# perfect_cubev2.net
KiCad netlist of a schematic drawn in EAGLE
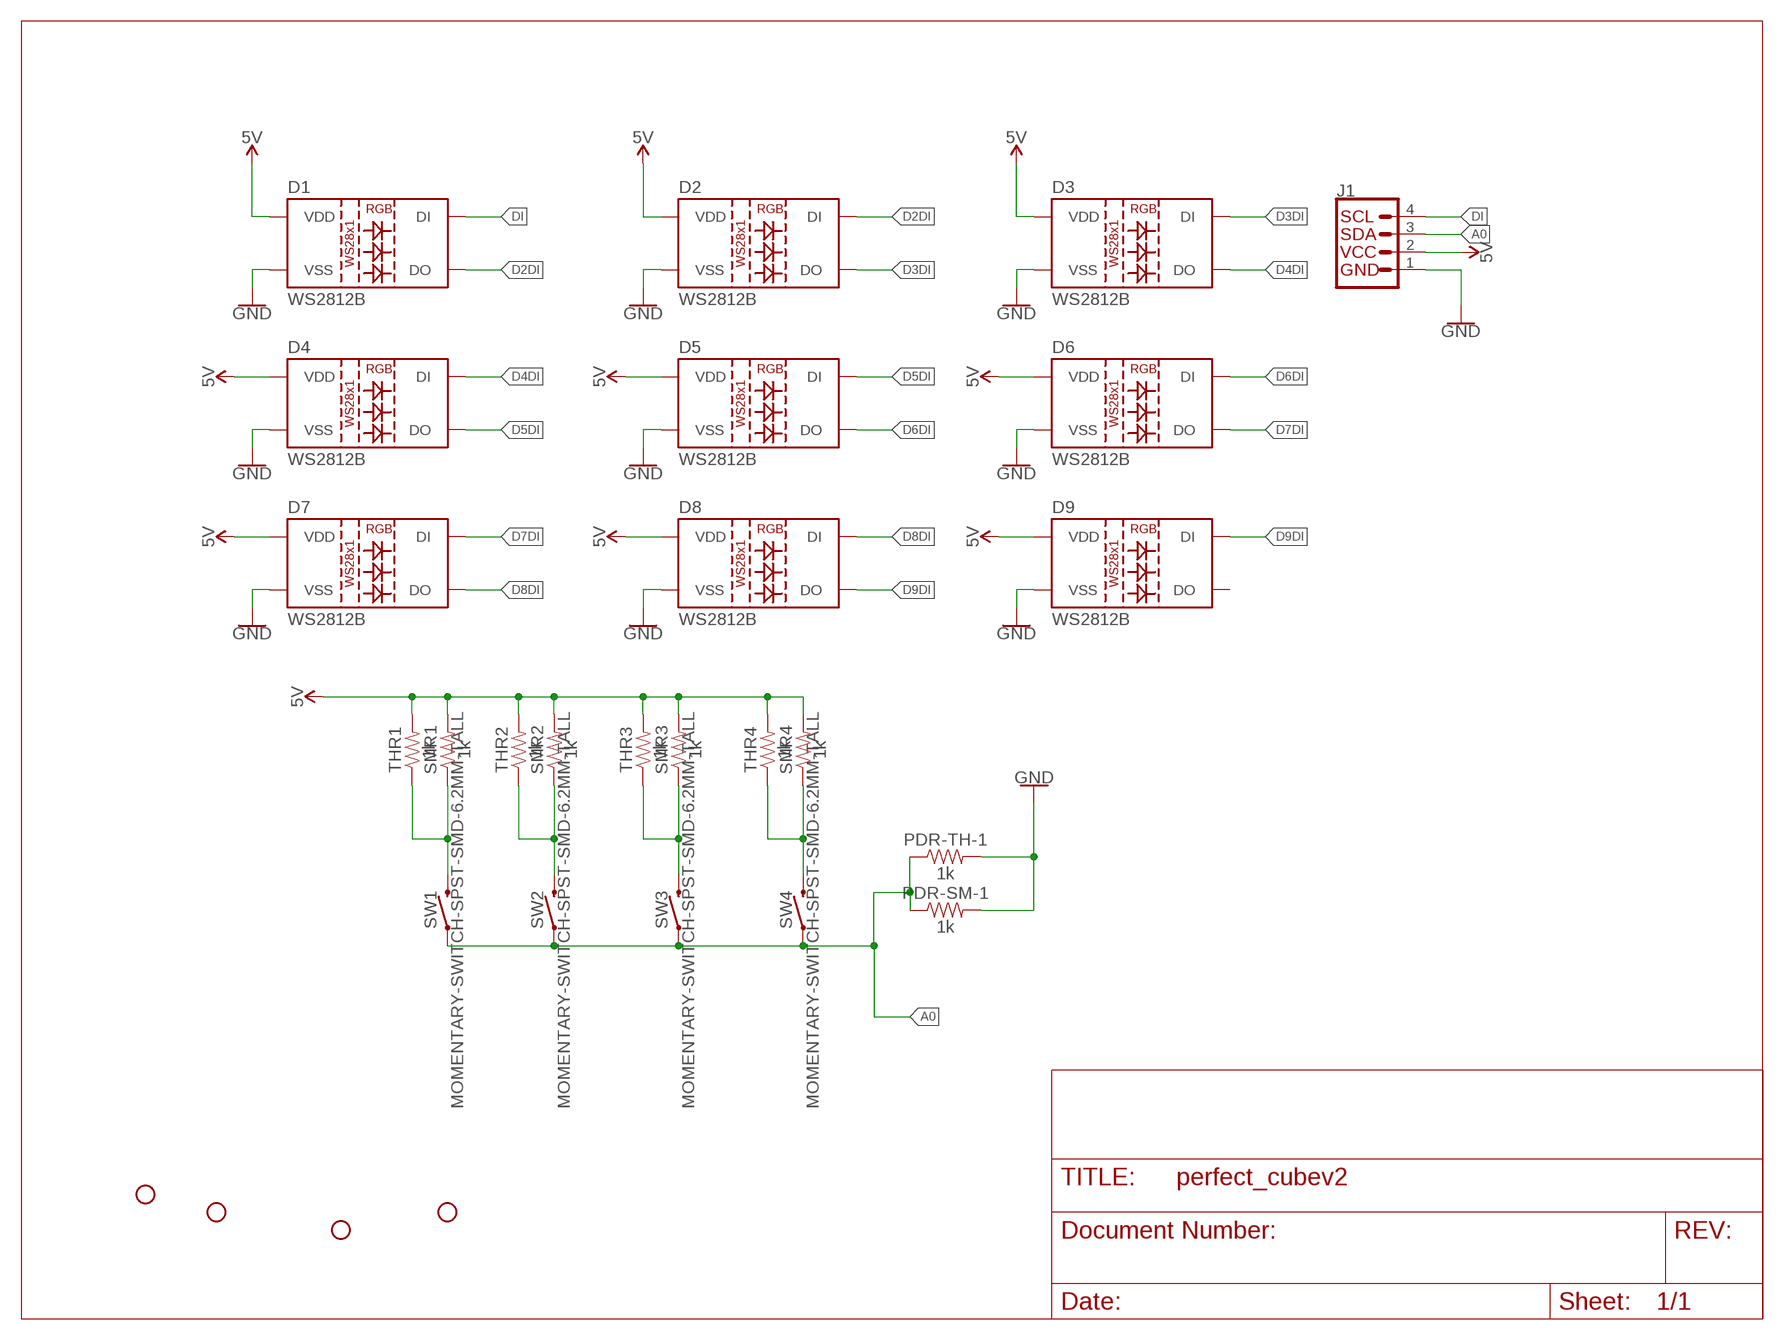
[diagram p0: schematic, sheet 1]

(export (version "E")
  (design (tool "Eeschema 10.0.6"))
  (components
    (comp (ref "D1")
      (value "WS2812B")
      (footprint "eagle-import:WS2812B")
      (libsource (lib "eagle-import") (part "WS2812B"))
    )
    (comp (ref "D2")
      (value "WS2812B")
      (footprint "eagle-import:WS2812B")
      (libsource (lib "eagle-import") (part "WS2812B"))
    )
    (comp (ref "D3")
      (value "WS2812B")
      (footprint "eagle-import:WS2812B")
      (libsource (lib "eagle-import") (part "WS2812B"))
    )
    (comp (ref "D4")
      (value "WS2812B")
      (footprint "eagle-import:WS2812B")
      (libsource (lib "eagle-import") (part "WS2812B"))
    )
    (comp (ref "D5")
      (value "WS2812B")
      (footprint "eagle-import:WS2812B")
      (libsource (lib "eagle-import") (part "WS2812B"))
    )
    (comp (ref "D6")
      (value "WS2812B")
      (footprint "eagle-import:WS2812B")
      (libsource (lib "eagle-import") (part "WS2812B"))
    )
    (comp (ref "D7")
      (value "WS2812B")
      (footprint "eagle-import:WS2812B")
      (libsource (lib "eagle-import") (part "WS2812B"))
    )
    (comp (ref "D8")
      (value "WS2812B")
      (footprint "eagle-import:WS2812B")
      (libsource (lib "eagle-import") (part "WS2812B"))
    )
    (comp (ref "D9")
      (value "WS2812B")
      (footprint "eagle-import:WS2812B")
      (libsource (lib "eagle-import") (part "WS2812B"))
    )
    (comp (ref "H1")
      (value "STAND-OFF")
      (footprint "eagle-import:STAND-OFF")
      (libsource (lib "eagle-import") (part "STAND-OFF"))
    )
    (comp (ref "H2")
      (value "STAND-OFF")
      (footprint "eagle-import:STAND-OFF")
      (libsource (lib "eagle-import") (part "STAND-OFF"))
    )
    (comp (ref "H3")
      (value "STAND-OFF")
      (footprint "eagle-import:STAND-OFF")
      (libsource (lib "eagle-import") (part "STAND-OFF"))
    )
    (comp (ref "H4")
      (value "STAND-OFF")
      (footprint "eagle-import:STAND-OFF")
      (libsource (lib "eagle-import") (part "STAND-OFF"))
    )
    (comp (ref "J1")
      (value "QWIIC_CONNECTORJS-1MM")
      (footprint "eagle-import:1X04_1MM_RA")
      (libsource (lib "eagle-import") (part "QWIIC_CONNECTORJS-1MM"))
    )
    (comp (ref "PDR-SM-1")
      (value "1k")
      (footprint "eagle-import:0603")
      (libsource (lib "eagle-import") (part "1KOHM-0603-1/10W-1%"))
    )
    (comp (ref "PDR-TH-1")
      (value "1k")
      (footprint "eagle-import:AXIAL-0.3")
      (libsource (lib "eagle-import") (part "1KOHM-HORIZ-1/4W-1%"))
    )
    (comp (ref "SMR1")
      (value "1k")
      (footprint "eagle-import:0603")
      (libsource (lib "eagle-import") (part "1KOHM-0603-1/10W-1%"))
    )
    (comp (ref "SMR2")
      (value "1k")
      (footprint "eagle-import:0603")
      (libsource (lib "eagle-import") (part "1KOHM-0603-1/10W-1%"))
    )
    (comp (ref "SMR3")
      (value "1k")
      (footprint "eagle-import:0603")
      (libsource (lib "eagle-import") (part "1KOHM-0603-1/10W-1%"))
    )
    (comp (ref "SMR4")
      (value "1k")
      (footprint "eagle-import:0603")
      (libsource (lib "eagle-import") (part "1KOHM-0603-1/10W-1%"))
    )
    (comp (ref "SW1")
      (value "MOMENTARY-SWITCH-SPST-SMD-6.2MM-TALL")
      (footprint "eagle-import:TACTILE_SWITCH_SMD_6.2MM_TALL")
      (libsource (lib "eagle-import") (part "MOMENTARY-SWITCH-SPST-SMD-6.2MM-TALL"))
    )
    (comp (ref "SW2")
      (value "MOMENTARY-SWITCH-SPST-SMD-6.2MM-TALL")
      (footprint "eagle-import:TACTILE_SWITCH_SMD_6.2MM_TALL")
      (libsource (lib "eagle-import") (part "MOMENTARY-SWITCH-SPST-SMD-6.2MM-TALL"))
    )
    (comp (ref "SW3")
      (value "MOMENTARY-SWITCH-SPST-SMD-6.2MM-TALL")
      (footprint "eagle-import:TACTILE_SWITCH_SMD_6.2MM_TALL")
      (libsource (lib "eagle-import") (part "MOMENTARY-SWITCH-SPST-SMD-6.2MM-TALL"))
    )
    (comp (ref "SW4")
      (value "MOMENTARY-SWITCH-SPST-SMD-6.2MM-TALL")
      (footprint "eagle-import:TACTILE_SWITCH_SMD_6.2MM_TALL")
      (libsource (lib "eagle-import") (part "MOMENTARY-SWITCH-SPST-SMD-6.2MM-TALL"))
    )
    (comp (ref "THR1")
      (value "1k")
      (footprint "eagle-import:AXIAL-0.3")
      (libsource (lib "eagle-import") (part "1KOHM-HORIZ-1/4W-1%"))
    )
    (comp (ref "THR2")
      (value "1k")
      (footprint "eagle-import:AXIAL-0.3")
      (libsource (lib "eagle-import") (part "1KOHM-HORIZ-1/4W-1%"))
    )
    (comp (ref "THR3")
      (value "1k")
      (footprint "eagle-import:AXIAL-0.3")
      (libsource (lib "eagle-import") (part "1KOHM-HORIZ-1/4W-1%"))
    )
    (comp (ref "THR4")
      (value "1k")
      (footprint "eagle-import:AXIAL-0.3")
      (libsource (lib "eagle-import") (part "1KOHM-HORIZ-1/4W-1%"))
    )
  )
  (nets
    (net (code "1") (name "5V") (class "Default")
      (node (ref "D1") (pin "1") (pinfunction "VDD_1") (pintype "bidirectional"))
      (node (ref "D2") (pin "1") (pinfunction "VDD_1") (pintype "bidirectional"))
      (node (ref "D3") (pin "1") (pinfunction "VDD_1") (pintype "bidirectional"))
      (node (ref "D4") (pin "1") (pinfunction "VDD_1") (pintype "bidirectional"))
      (node (ref "D5") (pin "1") (pinfunction "VDD_1") (pintype "bidirectional"))
      (node (ref "D6") (pin "1") (pinfunction "VDD_1") (pintype "bidirectional"))
      (node (ref "D7") (pin "1") (pinfunction "VDD_1") (pintype "bidirectional"))
      (node (ref "D8") (pin "1") (pinfunction "VDD_1") (pintype "bidirectional"))
      (node (ref "D9") (pin "1") (pinfunction "VDD_1") (pintype "bidirectional"))
      (node (ref "J1") (pin "2") (pinfunction "VCC_2") (pintype "power_in"))
      (node (ref "SMR1") (pin "2") (pinfunction "2_2") (pintype "passive"))
      (node (ref "SMR2") (pin "2") (pinfunction "2_2") (pintype "passive"))
      (node (ref "SMR3") (pin "2") (pinfunction "2_2") (pintype "passive"))
      (node (ref "SMR4") (pin "2") (pinfunction "2_2") (pintype "passive"))
      (node (ref "THR1") (pin "P$2") (pinfunction "2_P$2") (pintype "passive"))
      (node (ref "THR2") (pin "P$2") (pinfunction "2_P$2") (pintype "passive"))
      (node (ref "THR3") (pin "P$2") (pinfunction "2_P$2") (pintype "passive"))
      (node (ref "THR4") (pin "P$2") (pinfunction "2_P$2") (pintype "passive"))
    )
    (net (code "2") (name "A0") (class "Default")
      (node (ref "J1") (pin "3") (pinfunction "SDA_3") (pintype "passive"))
      (node (ref "PDR-SM-1") (pin "1") (pinfunction "1_1") (pintype "passive"))
      (node (ref "PDR-TH-1") (pin "P$1") (pinfunction "1_P$1") (pintype "passive"))
      (node (ref "SW1") (pin "A2") (pinfunction "1_A2") (pintype "passive"))
      (node (ref "SW2") (pin "A2") (pinfunction "1_A2") (pintype "passive"))
      (node (ref "SW3") (pin "A2") (pinfunction "1_A2") (pintype "passive"))
      (node (ref "SW4") (pin "A2") (pinfunction "1_A2") (pintype "passive"))
    )
    (net (code "3") (name "D2DI") (class "Default")
      (node (ref "D1") (pin "2") (pinfunction "DO_2") (pintype "bidirectional"))
      (node (ref "D2") (pin "4") (pinfunction "DI_4") (pintype "bidirectional"))
    )
    (net (code "4") (name "D3DI") (class "Default")
      (node (ref "D2") (pin "2") (pinfunction "DO_2") (pintype "bidirectional"))
      (node (ref "D3") (pin "4") (pinfunction "DI_4") (pintype "bidirectional"))
    )
    (net (code "5") (name "D4DI") (class "Default")
      (node (ref "D3") (pin "2") (pinfunction "DO_2") (pintype "bidirectional"))
      (node (ref "D4") (pin "4") (pinfunction "DI_4") (pintype "bidirectional"))
    )
    (net (code "6") (name "D5DI") (class "Default")
      (node (ref "D4") (pin "2") (pinfunction "DO_2") (pintype "bidirectional"))
      (node (ref "D5") (pin "4") (pinfunction "DI_4") (pintype "bidirectional"))
    )
    (net (code "7") (name "D6DI") (class "Default")
      (node (ref "D5") (pin "2") (pinfunction "DO_2") (pintype "bidirectional"))
      (node (ref "D6") (pin "4") (pinfunction "DI_4") (pintype "bidirectional"))
    )
    (net (code "8") (name "D7DI") (class "Default")
      (node (ref "D6") (pin "2") (pinfunction "DO_2") (pintype "bidirectional"))
      (node (ref "D7") (pin "4") (pinfunction "DI_4") (pintype "bidirectional"))
    )
    (net (code "9") (name "D8DI") (class "Default")
      (node (ref "D7") (pin "2") (pinfunction "DO_2") (pintype "bidirectional"))
      (node (ref "D8") (pin "4") (pinfunction "DI_4") (pintype "bidirectional"))
    )
    (net (code "10") (name "D9DI") (class "Default")
      (node (ref "D8") (pin "2") (pinfunction "DO_2") (pintype "bidirectional"))
      (node (ref "D9") (pin "4") (pinfunction "DI_4") (pintype "bidirectional"))
    )
    (net (code "11") (name "DI") (class "Default")
      (node (ref "D1") (pin "4") (pinfunction "DI_4") (pintype "bidirectional"))
      (node (ref "J1") (pin "4") (pinfunction "SCL_4") (pintype "passive"))
    )
    (net (code "12") (name "GND") (class "Default")
      (node (ref "D1") (pin "3") (pinfunction "VSS_3") (pintype "bidirectional"))
      (node (ref "D2") (pin "3") (pinfunction "VSS_3") (pintype "bidirectional"))
      (node (ref "D3") (pin "3") (pinfunction "VSS_3") (pintype "bidirectional"))
      (node (ref "D4") (pin "3") (pinfunction "VSS_3") (pintype "bidirectional"))
      (node (ref "D5") (pin "3") (pinfunction "VSS_3") (pintype "bidirectional"))
      (node (ref "D6") (pin "3") (pinfunction "VSS_3") (pintype "bidirectional"))
      (node (ref "D7") (pin "3") (pinfunction "VSS_3") (pintype "bidirectional"))
      (node (ref "D8") (pin "3") (pinfunction "VSS_3") (pintype "bidirectional"))
      (node (ref "D9") (pin "3") (pinfunction "VSS_3") (pintype "bidirectional"))
      (node (ref "J1") (pin "1") (pinfunction "GND_1") (pintype "power_in"))
      (node (ref "PDR-SM-1") (pin "2") (pinfunction "2_2") (pintype "passive"))
      (node (ref "PDR-TH-1") (pin "P$2") (pinfunction "2_P$2") (pintype "passive"))
    )
    (net (code "13") (name "Net-(SW1-2)") (class "Default")
      (node (ref "SMR1") (pin "1") (pinfunction "1_1") (pintype "passive"))
      (node (ref "SW1") (pin "B2") (pinfunction "2_B2") (pintype "passive"))
      (node (ref "THR1") (pin "P$1") (pinfunction "1_P$1") (pintype "passive"))
    )
    (net (code "14") (name "Net-(SW2-2)") (class "Default")
      (node (ref "SMR2") (pin "1") (pinfunction "1_1") (pintype "passive"))
      (node (ref "SW2") (pin "B2") (pinfunction "2_B2") (pintype "passive"))
      (node (ref "THR2") (pin "P$1") (pinfunction "1_P$1") (pintype "passive"))
    )
    (net (code "15") (name "Net-(SW3-2)") (class "Default")
      (node (ref "SMR3") (pin "1") (pinfunction "1_1") (pintype "passive"))
      (node (ref "SW3") (pin "B2") (pinfunction "2_B2") (pintype "passive"))
      (node (ref "THR3") (pin "P$1") (pinfunction "1_P$1") (pintype "passive"))
    )
    (net (code "16") (name "Net-(SW4-2)") (class "Default")
      (node (ref "SMR4") (pin "1") (pinfunction "1_1") (pintype "passive"))
      (node (ref "SW4") (pin "B2") (pinfunction "2_B2") (pintype "passive"))
      (node (ref "THR4") (pin "P$1") (pinfunction "1_P$1") (pintype "passive"))
    )
    (net (code "17") (name "unconnected-(D9-DO-Pad2)") (class "Default")
      (node (ref "D9") (pin "2") (pinfunction "DO_2") (pintype "bidirectional"))
    )
  )
)
